# BATTERY_BOARD_K6T6.net
KiCad netlist of a schematic drawn in Altium Designer
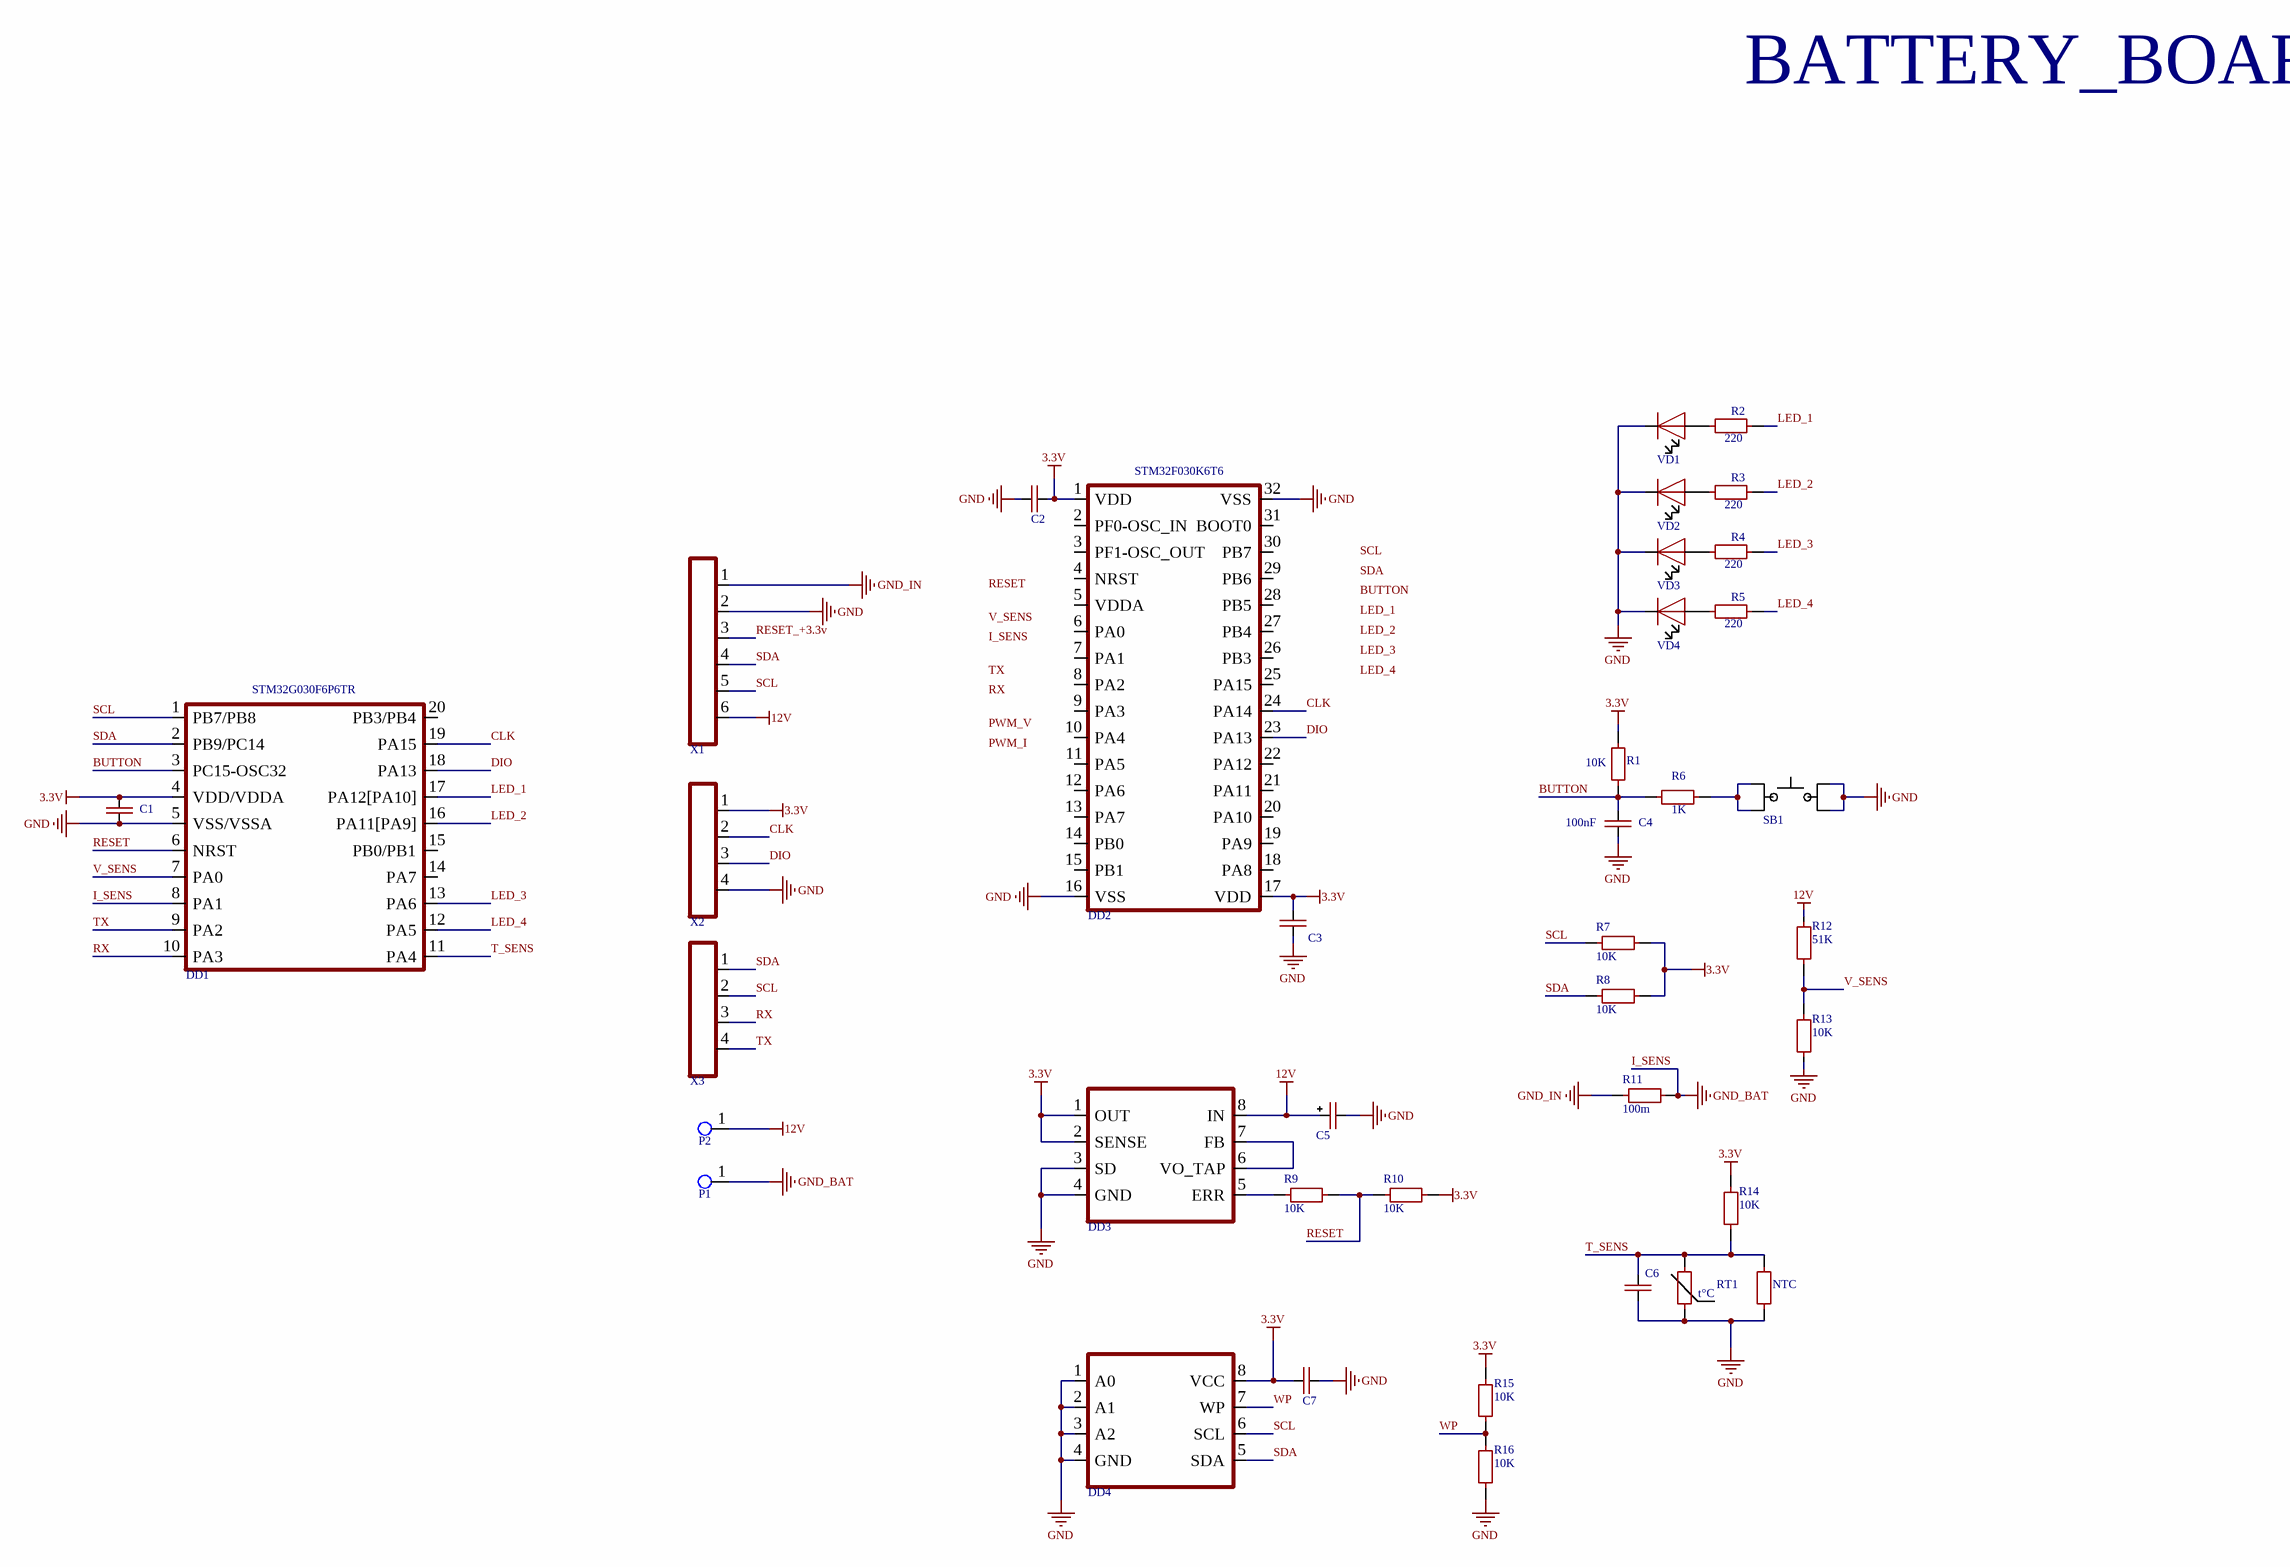
[diagram p0: BATTERY_BOARD_K6T6.SchDoc]

(export (version "E")
  (design (tool "Eeschema 10.0.6"))
  (components
    (comp (ref "C1")
      (value "CAP-NON-POLAR")
      (footprint "CAP-0603")
      (libsource (lib "PASSIVE_COMPONENTS") (part "CAP-NON-POLAR"))
    )
    (comp (ref "C2")
      (value "CAP-NON-POLAR")
      (footprint "CAP-0603")
      (libsource (lib "PASSIVE_COMPONENTS") (part "CAP-NON-POLAR"))
    )
    (comp (ref "C3")
      (value "CAP-NON-POLAR")
      (footprint "CAP-0603")
      (libsource (lib "PASSIVE_COMPONENTS") (part "CAP-NON-POLAR"))
    )
    (comp (ref "C4")
      (value "100nF")
      (footprint "CAP-0603")
      (libsource (lib "PASSIVE_COMPONENTS") (part "CAP-NON-POLAR"))
    )
    (comp (ref "C5")
      (value "CAP-POLAR")
      (footprint "CAP-TAN-C")
      (libsource (lib "PASSIVE_COMPONENTS") (part "CAP-POLAR"))
    )
    (comp (ref "C6")
      (value "CAP-NON-POLAR")
      (footprint "CAP-0805")
      (libsource (lib "PASSIVE_COMPONENTS") (part "CAP-NON-POLAR"))
    )
    (comp (ref "C7")
      (value "CAP-NON-POLAR")
      (footprint "CAP-0603")
      (libsource (lib "PASSIVE_COMPONENTS") (part "CAP-NON-POLAR"))
    )
    (comp (ref "DD1")
      (value "STM32G030F6P6TR")
      (footprint "TSSOP-20")
      (libsource (lib "STM32G030F6P6TR") (part "STM32G030F6P6TR"))
    )
    (comp (ref "DD2")
      (value "STM32F030K6T6")
      (footprint "LQFP32")
      (libsource (lib "STM32F030K6T6") (part "STM32F030K6T6"))
    )
    (comp (ref "DD3") (value "LP2951") (footprint "SO8-150") (libsource (lib "LP2951") (part "LP2951")))
    (comp (ref "DD4") (value "24C256") (footprint "SO8-150") (libsource (lib "24C256") (part "24C256")))
    (comp (ref "NTC")
      (value "RES-CONST")
      (footprint "RES-0805")
      (libsource (lib "PASSIVE_COMPONENTS") (part "RES-CONST"))
    )
    (comp (ref "P1") (value "Test_Point_PCB") (footprint "Point") (libsource (lib "POINT") (part "POINT")))
    (comp (ref "P2") (value "Test_Point_PCB") (footprint "Point") (libsource (lib "POINT") (part "POINT")))
    (comp (ref "R1")
      (value "10K")
      (footprint "RES-0603")
      (libsource (lib "PASSIVE_COMPONENTS") (part "RES-CONST"))
    )
    (comp (ref "R2")
      (value "220")
      (footprint "RES-0603")
      (libsource (lib "PASSIVE_COMPONENTS") (part "RES-CONST"))
    )
    (comp (ref "R3")
      (value "220")
      (footprint "RES-0603")
      (libsource (lib "PASSIVE_COMPONENTS") (part "RES-CONST"))
    )
    (comp (ref "R4")
      (value "220")
      (footprint "RES-0603")
      (libsource (lib "PASSIVE_COMPONENTS") (part "RES-CONST"))
    )
    (comp (ref "R5")
      (value "220")
      (footprint "RES-0603")
      (libsource (lib "PASSIVE_COMPONENTS") (part "RES-CONST"))
    )
    (comp (ref "R6")
      (value "1K")
      (footprint "RES-0603")
      (libsource (lib "PASSIVE_COMPONENTS") (part "RES-CONST"))
    )
    (comp (ref "R7")
      (value "10K")
      (footprint "RES-0603")
      (libsource (lib "PASSIVE_COMPONENTS") (part "RES-CONST"))
    )
    (comp (ref "R8")
      (value "10K")
      (footprint "RES-0603")
      (libsource (lib "PASSIVE_COMPONENTS") (part "RES-CONST"))
    )
    (comp (ref "R9")
      (value "10K")
      (footprint "RES-0603")
      (libsource (lib "PASSIVE_COMPONENTS") (part "RES-CONST"))
    )
    (comp (ref "R10")
      (value "10K")
      (footprint "RES-0603")
      (libsource (lib "PASSIVE_COMPONENTS") (part "RES-CONST"))
    )
    (comp (ref "R11")
      (value "100m")
      (footprint "RES-2512")
      (libsource (lib "PASSIVE_COMPONENTS") (part "RES-CONST"))
    )
    (comp (ref "R12")
      (value "51K")
      (footprint "RES-0603")
      (libsource (lib "PASSIVE_COMPONENTS") (part "RES-CONST"))
    )
    (comp (ref "R13")
      (value "10K")
      (footprint "RES-0603")
      (libsource (lib "PASSIVE_COMPONENTS") (part "RES-CONST"))
    )
    (comp (ref "R14")
      (value "10K")
      (footprint "RES-0603")
      (libsource (lib "PASSIVE_COMPONENTS") (part "RES-CONST"))
    )
    (comp (ref "R15")
      (value "10K")
      (footprint "RES-0603")
      (libsource (lib "PASSIVE_COMPONENTS") (part "RES-CONST"))
    )
    (comp (ref "R16")
      (value "10K")
      (footprint "RES-0603")
      (libsource (lib "PASSIVE_COMPONENTS") (part "RES-CONST"))
    )
    (comp (ref "RT1") (value "RES-TEMP") (footprint "NTC_MF52") (libsource (lib "NTC") (part "RES-TEMP")))
    (comp (ref "SB1")
      (value "BUTTON-TACT-4PIN")
      (footprint "TACTB-6x6 SMD")
      (libsource (lib "TACTB-6x6 SMD") (part "BUTTON-TACT-4PIN"))
    )
    (comp (ref "VD1") (value "LED") (footprint "LED-0603") (libsource (lib "LED") (part "LED")))
    (comp (ref "VD2") (value "LED") (footprint "LED-0603") (libsource (lib "LED") (part "LED")))
    (comp (ref "VD3") (value "LED") (footprint "LED-0603") (libsource (lib "LED") (part "LED")))
    (comp (ref "VD4") (value "LED") (footprint "LED-0603") (libsource (lib "LED") (part "LED")))
    (comp (ref "X1")
      (value "CONN-6-PIN")
      (footprint "CON_6PIN_BATT_DEFIBRILLATOR")
      (libsource (lib "CON_6PIN_BATT_DEFIBRILLATOR") (part "CONN-6-PIN"))
    )
    (comp (ref "X2")
      (value "CONN-4-PIN")
      (footprint "CONN-PLS-4-2.54mm")
      (libsource (lib "CONNECTORS") (part "CONN-4-PIN"))
    )
    (comp (ref "X3")
      (value "CONN-4-PIN")
      (footprint "CONN-PLS-4-2.54mm")
      (libsource (lib "CONNECTORS") (part "CONN-4-PIN"))
    )
  )
  (nets
    (net (code "1") (name "/BUTTON") (class "Default")
      (node (ref "C4") (pin "2") (pinfunction "2_2") (pintype "passive"))
      (node (ref "DD1") (pin "3") (pinfunction "PC15-OSC32_3") (pintype "passive"))
      (node (ref "R1") (pin "1") (pinfunction "1_1") (pintype "passive"))
      (node (ref "R6") (pin "1") (pinfunction "1_1") (pintype "passive"))
    )
    (net (code "2") (name "/CLK") (class "Default")
      (node (ref "DD1") (pin "19") (pinfunction "PA15_19") (pintype "passive"))
      (node (ref "DD2") (pin "24") (pinfunction "PA14_24") (pintype "passive"))
      (node (ref "X2") (pin "2") (pinfunction "2_2") (pintype "passive"))
    )
    (net (code "3") (name "/DIO") (class "Default")
      (node (ref "DD1") (pin "18") (pinfunction "PA13_18") (pintype "passive"))
      (node (ref "DD2") (pin "23") (pinfunction "PA13_23") (pintype "passive"))
      (node (ref "X2") (pin "3") (pinfunction "3_3") (pintype "passive"))
    )
    (net (code "4") (name "/LED_1") (class "Default")
      (node (ref "DD1") (pin "17") (pinfunction "PA12[PA10]_17") (pintype "passive"))
      (node (ref "R2") (pin "2") (pinfunction "2_2") (pintype "passive"))
    )
    (net (code "5") (name "/LED_2") (class "Default")
      (node (ref "DD1") (pin "16") (pinfunction "PA11[PA9]_16") (pintype "passive"))
      (node (ref "R3") (pin "2") (pinfunction "2_2") (pintype "passive"))
    )
    (net (code "6") (name "/LED_3") (class "Default")
      (node (ref "DD1") (pin "13") (pinfunction "PA6_13") (pintype "passive"))
      (node (ref "R4") (pin "2") (pinfunction "2_2") (pintype "passive"))
    )
    (net (code "7") (name "/LED_4") (class "Default")
      (node (ref "DD1") (pin "12") (pinfunction "PA5_12") (pintype "passive"))
      (node (ref "R5") (pin "2") (pinfunction "2_2") (pintype "passive"))
    )
    (net (code "10") (name "/RESET") (class "Default")
      (node (ref "DD1") (pin "6") (pinfunction "NRST_6") (pintype "passive"))
      (node (ref "R10") (pin "2") (pinfunction "2_2") (pintype "passive"))
      (node (ref "R9") (pin "1") (pinfunction "1_1") (pintype "passive"))
    )
    (net (code "11") (name "/RESET_+3.3v") (class "Default")
      (node (ref "X1") (pin "3") (pinfunction "3_3") (pintype "passive"))
    )
    (net (code "12") (name "/RX") (class "Default")
      (node (ref "DD1") (pin "10") (pinfunction "PA3_10") (pintype "passive"))
      (node (ref "X3") (pin "3") (pinfunction "3_3") (pintype "passive"))
    )
    (net (code "13") (name "/SCL") (class "Default")
      (node (ref "DD1") (pin "1") (pinfunction "PB7/PB8_1") (pintype "passive"))
      (node (ref "DD4") (pin "6") (pinfunction "SCL_6") (pintype "passive"))
      (node (ref "R7") (pin "2") (pinfunction "2_2") (pintype "passive"))
      (node (ref "X1") (pin "5") (pinfunction "5_5") (pintype "passive"))
      (node (ref "X3") (pin "2") (pinfunction "2_2") (pintype "passive"))
    )
    (net (code "14") (name "/SDA") (class "Default")
      (node (ref "DD1") (pin "2") (pinfunction "PB9/PC14_2") (pintype "passive"))
      (node (ref "DD4") (pin "5") (pinfunction "SDA_5") (pintype "passive"))
      (node (ref "R8") (pin "2") (pinfunction "2_2") (pintype "passive"))
      (node (ref "X1") (pin "4") (pinfunction "4_4") (pintype "passive"))
      (node (ref "X3") (pin "1") (pinfunction "1_1") (pintype "passive"))
    )
    (net (code "15") (name "/TX") (class "Default")
      (node (ref "DD1") (pin "9") (pinfunction "PA2_9") (pintype "passive"))
      (node (ref "X3") (pin "4") (pinfunction "4_4") (pintype "passive"))
    )
    (net (code "16") (name "/T_SENS") (class "Default")
      (node (ref "C6") (pin "2") (pinfunction "2_2") (pintype "passive"))
      (node (ref "DD1") (pin "11") (pinfunction "PA4_11") (pintype "passive"))
      (node (ref "NTC") (pin "2") (pinfunction "2_2") (pintype "passive"))
      (node (ref "R14") (pin "2") (pinfunction "2_2") (pintype "passive"))
      (node (ref "RT1") (pin "2") (pinfunction "2_2") (pintype "passive"))
    )
    (net (code "17") (name "/V_SENS") (class "Default")
      (node (ref "DD1") (pin "7") (pinfunction "PA0_7") (pintype "passive"))
      (node (ref "R12") (pin "2") (pinfunction "2_2") (pintype "passive"))
      (node (ref "R13") (pin "1") (pinfunction "1_1") (pintype "passive"))
    )
    (net (code "18") (name "/WP") (class "Default")
      (node (ref "DD4") (pin "7") (pinfunction "WP_7") (pintype "passive"))
      (node (ref "R15") (pin "2") (pinfunction "2_2") (pintype "passive"))
      (node (ref "R16") (pin "1") (pinfunction "1_1") (pintype "passive"))
    )
    (net (code "19") (name "3.3V") (class "Default")
      (node (ref "C1") (pin "2") (pinfunction "2_2") (pintype "passive"))
      (node (ref "C2") (pin "2") (pinfunction "2_2") (pintype "passive"))
      (node (ref "C3") (pin "2") (pinfunction "2_2") (pintype "passive"))
      (node (ref "C7") (pin "2") (pinfunction "2_2") (pintype "passive"))
      (node (ref "DD1") (pin "4") (pinfunction "VDD/VDDA_4") (pintype "passive"))
      (node (ref "DD2") (pin "1") (pinfunction "VDD_1") (pintype "passive"))
      (node (ref "DD2") (pin "17") (pinfunction "VDD_17") (pintype "passive"))
      (node (ref "DD3") (pin "1") (pinfunction "OUT_1") (pintype "passive"))
      (node (ref "DD3") (pin "2") (pinfunction "SENSE_2") (pintype "passive"))
      (node (ref "DD4") (pin "8") (pinfunction "VCC_8") (pintype "passive"))
      (node (ref "R1") (pin "2") (pinfunction "2_2") (pintype "passive"))
      (node (ref "R10") (pin "1") (pinfunction "1_1") (pintype "passive"))
      (node (ref "R14") (pin "1") (pinfunction "1_1") (pintype "passive"))
      (node (ref "R15") (pin "1") (pinfunction "1_1") (pintype "passive"))
      (node (ref "R7") (pin "1") (pinfunction "1_1") (pintype "passive"))
      (node (ref "R8") (pin "1") (pinfunction "1_1") (pintype "passive"))
      (node (ref "X2") (pin "1") (pinfunction "1_1") (pintype "passive"))
    )
    (net (code "20") (name "12V") (class "Default")
      (node (ref "C5") (pin "1") (pinfunction "+_1") (pintype "passive"))
      (node (ref "DD3") (pin "8") (pinfunction "IN_8") (pintype "passive"))
      (node (ref "P2") (pin "1") (pinfunction "G9_1") (pintype "passive"))
      (node (ref "R12") (pin "1") (pinfunction "1_1") (pintype "passive"))
      (node (ref "X1") (pin "6") (pinfunction "6_6") (pintype "passive"))
    )
    (net (code "21") (name "GND") (class "Default")
      (node (ref "C1") (pin "1") (pinfunction "1_1") (pintype "passive"))
      (node (ref "C2") (pin "1") (pinfunction "1_1") (pintype "passive"))
      (node (ref "C3") (pin "1") (pinfunction "1_1") (pintype "passive"))
      (node (ref "C4") (pin "1") (pinfunction "1_1") (pintype "passive"))
      (node (ref "C5") (pin "2") (pinfunction "-_2") (pintype "passive"))
      (node (ref "C6") (pin "1") (pinfunction "1_1") (pintype "passive"))
      (node (ref "C7") (pin "1") (pinfunction "1_1") (pintype "passive"))
      (node (ref "DD1") (pin "5") (pinfunction "VSS/VSSA_5") (pintype "passive"))
      (node (ref "DD2") (pin "16") (pinfunction "VSS_16") (pintype "passive"))
      (node (ref "DD2") (pin "32") (pinfunction "VSS_32") (pintype "passive"))
      (node (ref "DD3") (pin "3") (pinfunction "SD_3") (pintype "passive"))
      (node (ref "DD3") (pin "4") (pinfunction "GND_4") (pintype "passive"))
      (node (ref "DD4") (pin "1") (pinfunction "A0_1") (pintype "passive"))
      (node (ref "DD4") (pin "2") (pinfunction "A1_2") (pintype "passive"))
      (node (ref "DD4") (pin "3") (pinfunction "A2_3") (pintype "passive"))
      (node (ref "DD4") (pin "4") (pinfunction "GND_4") (pintype "passive"))
      (node (ref "NTC") (pin "1") (pinfunction "1_1") (pintype "passive"))
      (node (ref "R13") (pin "2") (pinfunction "2_2") (pintype "passive"))
      (node (ref "R16") (pin "2") (pinfunction "2_2") (pintype "passive"))
      (node (ref "RT1") (pin "1") (pinfunction "1_1") (pintype "passive"))
      (node (ref "SB1") (pin "3") (pintype "passive"))
      (node (ref "SB1") (pin "4") (pintype "passive"))
      (node (ref "VD1") (pin "1") (pinfunction "C_1") (pintype "passive"))
      (node (ref "VD2") (pin "1") (pinfunction "C_1") (pintype "passive"))
      (node (ref "VD3") (pin "1") (pinfunction "C_1") (pintype "passive"))
      (node (ref "VD4") (pin "1") (pinfunction "C_1") (pintype "passive"))
      (node (ref "X1") (pin "2") (pinfunction "2_2") (pintype "passive"))
      (node (ref "X2") (pin "4") (pinfunction "4_4") (pintype "passive"))
    )
    (net (code "22") (name "GND_BAT") (class "Default")
      (node (ref "DD1") (pin "8") (pinfunction "PA1_8") (pintype "passive"))
      (node (ref "P1") (pin "1") (pinfunction "G9_1") (pintype "passive"))
      (node (ref "R11") (pin "2") (pinfunction "2_2") (pintype "passive"))
    )
    (net (code "23") (name "GND_IN") (class "Default")
      (node (ref "R11") (pin "1") (pinfunction "1_1") (pintype "passive"))
      (node (ref "X1") (pin "1") (pinfunction "1_1") (pintype "passive"))
    )
    (net (code "24") (name "Net-(DD3-ERR)") (class "Default")
      (node (ref "DD3") (pin "5") (pinfunction "ERR_5") (pintype "passive"))
      (node (ref "R9") (pin "2") (pinfunction "2_2") (pintype "passive"))
    )
    (net (code "25") (name "Net-(DD3-FB)") (class "Default")
      (node (ref "DD3") (pin "6") (pinfunction "VO_TAP_6") (pintype "passive"))
      (node (ref "DD3") (pin "7") (pinfunction "FB_7") (pintype "passive"))
    )
    (net (code "26") (name "Net-(R6-Pad2)") (class "Default")
      (node (ref "R6") (pin "2") (pinfunction "2_2") (pintype "passive"))
      (node (ref "SB1") (pin "1") (pintype "passive"))
      (node (ref "SB1") (pin "2") (pintype "passive"))
    )
    (net (code "27") (name "Net-(VD1-A)") (class "Default")
      (node (ref "R2") (pin "1") (pinfunction "1_1") (pintype "passive"))
      (node (ref "VD1") (pin "2") (pinfunction "A_2") (pintype "passive"))
    )
    (net (code "28") (name "Net-(VD2-A)") (class "Default")
      (node (ref "R3") (pin "1") (pinfunction "1_1") (pintype "passive"))
      (node (ref "VD2") (pin "2") (pinfunction "A_2") (pintype "passive"))
    )
    (net (code "29") (name "Net-(VD3-A)") (class "Default")
      (node (ref "R4") (pin "1") (pinfunction "1_1") (pintype "passive"))
      (node (ref "VD3") (pin "2") (pinfunction "A_2") (pintype "passive"))
    )
    (net (code "30") (name "Net-(VD4-A)") (class "Default")
      (node (ref "R5") (pin "1") (pinfunction "1_1") (pintype "passive"))
      (node (ref "VD4") (pin "2") (pinfunction "A_2") (pintype "passive"))
    )
    (net (code "31") (name "unconnected-(DD1-PA7-Pad14)") (class "Default")
      (node (ref "DD1") (pin "14") (pinfunction "PA7_14") (pintype "passive"))
    )
    (net (code "32") (name "unconnected-(DD1-PB0{slash}PB1-Pad15)") (class "Default")
      (node (ref "DD1") (pin "15") (pinfunction "PB0/PB1_15") (pintype "passive"))
    )
    (net (code "33") (name "unconnected-(DD1-PB3{slash}PB4-Pad20)") (class "Default")
      (node (ref "DD1") (pin "20") (pinfunction "PB3/PB4_20") (pintype "passive"))
    )
    (net (code "34") (name "unconnected-(DD2-BOOT0-Pad31)") (class "Default")
      (node (ref "DD2") (pin "31") (pinfunction "BOOT0_31") (pintype "passive"))
    )
    (net (code "35") (name "unconnected-(DD2-NRST-Pad4)") (class "Default")
      (node (ref "DD2") (pin "4") (pinfunction "NRST_4") (pintype "passive"))
    )
    (net (code "36") (name "unconnected-(DD2-PA0-Pad6)") (class "Default")
      (node (ref "DD2") (pin "6") (pinfunction "PA0_6") (pintype "passive"))
    )
    (net (code "37") (name "unconnected-(DD2-PA1-Pad7)") (class "Default")
      (node (ref "DD2") (pin "7") (pinfunction "PA1_7") (pintype "passive"))
    )
    (net (code "38") (name "unconnected-(DD2-PA2-Pad8)") (class "Default")
      (node (ref "DD2") (pin "8") (pinfunction "PA2_8") (pintype "passive"))
    )
    (net (code "39") (name "unconnected-(DD2-PA3-Pad9)") (class "Default")
      (node (ref "DD2") (pin "9") (pinfunction "PA3_9") (pintype "passive"))
    )
    (net (code "40") (name "unconnected-(DD2-PA4-Pad10)") (class "Default")
      (node (ref "DD2") (pin "10") (pinfunction "PA4_10") (pintype "passive"))
    )
    (net (code "41") (name "unconnected-(DD2-PA5-Pad11)") (class "Default")
      (node (ref "DD2") (pin "11") (pinfunction "PA5_11") (pintype "passive"))
    )
    (net (code "42") (name "unconnected-(DD2-PA6-Pad12)") (class "Default")
      (node (ref "DD2") (pin "12") (pinfunction "PA6_12") (pintype "passive"))
    )
    (net (code "43") (name "unconnected-(DD2-PA7-Pad13)") (class "Default")
      (node (ref "DD2") (pin "13") (pinfunction "PA7_13") (pintype "passive"))
    )
    (net (code "44") (name "unconnected-(DD2-PA8-Pad18)") (class "Default")
      (node (ref "DD2") (pin "18") (pinfunction "PA8_18") (pintype "passive"))
    )
    (net (code "45") (name "unconnected-(DD2-PA9-Pad19)") (class "Default")
      (node (ref "DD2") (pin "19") (pinfunction "PA9_19") (pintype "passive"))
    )
    (net (code "46") (name "unconnected-(DD2-PA10-Pad20)") (class "Default")
      (node (ref "DD2") (pin "20") (pinfunction "PA10_20") (pintype "passive"))
    )
    (net (code "47") (name "unconnected-(DD2-PA11-Pad21)") (class "Default")
      (node (ref "DD2") (pin "21") (pinfunction "PA11_21") (pintype "passive"))
    )
    (net (code "48") (name "unconnected-(DD2-PA12-Pad22)") (class "Default")
      (node (ref "DD2") (pin "22") (pinfunction "PA12_22") (pintype "passive"))
    )
    (net (code "49") (name "unconnected-(DD2-PA15-Pad25)") (class "Default")
      (node (ref "DD2") (pin "25") (pinfunction "PA15_25") (pintype "passive"))
    )
    (net (code "50") (name "unconnected-(DD2-PB0-Pad14)") (class "Default")
      (node (ref "DD2") (pin "14") (pinfunction "PB0_14") (pintype "passive"))
    )
    (net (code "51") (name "unconnected-(DD2-PB1-Pad15)") (class "Default")
      (node (ref "DD2") (pin "15") (pinfunction "PB1_15") (pintype "passive"))
    )
    (net (code "52") (name "unconnected-(DD2-PB3-Pad26)") (class "Default")
      (node (ref "DD2") (pin "26") (pinfunction "PB3_26") (pintype "passive"))
    )
    (net (code "53") (name "unconnected-(DD2-PB4-Pad27)") (class "Default")
      (node (ref "DD2") (pin "27") (pinfunction "PB4_27") (pintype "passive"))
    )
    (net (code "54") (name "unconnected-(DD2-PB5-Pad28)") (class "Default")
      (node (ref "DD2") (pin "28") (pinfunction "PB5_28") (pintype "passive"))
    )
    (net (code "55") (name "unconnected-(DD2-PB6-Pad29)") (class "Default")
      (node (ref "DD2") (pin "29") (pinfunction "PB6_29") (pintype "passive"))
    )
    (net (code "56") (name "unconnected-(DD2-PB7-Pad30)") (class "Default")
      (node (ref "DD2") (pin "30") (pinfunction "PB7_30") (pintype "passive"))
    )
    (net (code "57") (name "unconnected-(DD2-PF0-OSC_IN-Pad2)") (class "Default")
      (node (ref "DD2") (pin "2") (pinfunction "PF0-OSC_IN_2") (pintype "passive"))
    )
    (net (code "58") (name "unconnected-(DD2-PF1-OSC_OUT-Pad3)") (class "Default")
      (node (ref "DD2") (pin "3") (pinfunction "PF1-OSC_OUT_3") (pintype "passive"))
    )
    (net (code "59") (name "unconnected-(DD2-VDDA-Pad5)") (class "Default")
      (node (ref "DD2") (pin "5") (pinfunction "VDDA_5") (pintype "passive"))
    )
  )
)
